# Power.net
KiCad netlist of a schematic drawn in Altium Designer
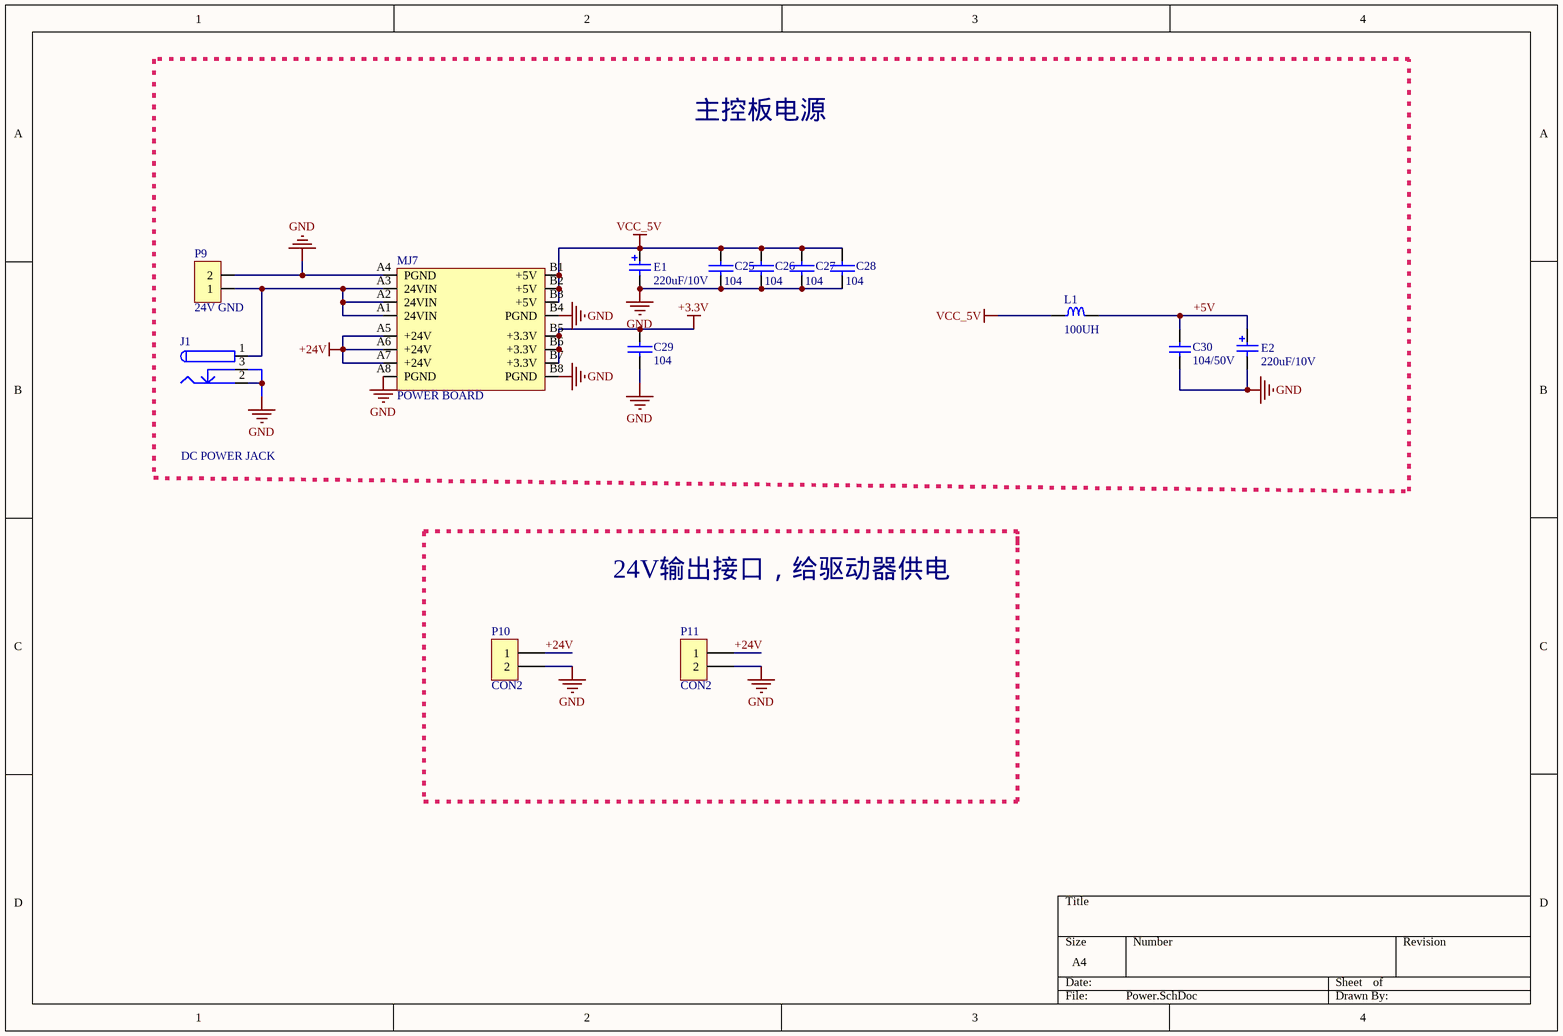
[diagram p0: Power.SchDoc]

(export (version "E")
  (design (tool "Eeschema 10.0.6"))
  (components
    (comp (ref "C25")
      (value "104")
      (footprint "0603C")
      (description "Capacitor")
      (libsource (lib "*") (part "CAP"))
    )
    (comp (ref "C26")
      (value "104")
      (footprint "0603C")
      (description "Capacitor")
      (libsource (lib "*") (part "CAP"))
    )
    (comp (ref "C27")
      (value "104")
      (footprint "0603C")
      (description "Capacitor")
      (libsource (lib "*") (part "CAP"))
    )
    (comp (ref "C28")
      (value "104")
      (footprint "0603C")
      (description "Capacitor")
      (libsource (lib "*") (part "CAP"))
    )
    (comp (ref "C29") (value "104") (footprint "0603C") (libsource (lib "WeiCHGSCH") (part "CAP")))
    (comp (ref "C30")
      (value "104/50V")
      (footprint "0603C")
      (description "瓷片电容,10uF,5%,X7R,50V,0805")
      (libsource (lib "SR SCH Library V02") (part "C10uF/50V-0805"))
    )
    (comp (ref "E1")
      (value "220uF/10V")
      (footprint "3216")
      (description "Bi-Polar Capacitor")
      (libsource (lib "*") (part "电解电容"))
    )
    (comp (ref "E2")
      (value "220uF/10V")
      (footprint "3216")
      (description "Bi-Polar Capacitor")
      (libsource (lib "*") (part "电解电容"))
    )
    (comp (ref "J1")
      (value "DC POWER JACK")
      (footprint "DC-005")
      (libsource (lib "WeiCHGSCH") (part "DC POWER JACK"))
    )
    (comp (ref "L1")
      (value "100UH")
      (footprint "L-SMD7.4*7.4")
      (description "电感")
      (libsource (lib "*") (part "INDUCTOR"))
    )
    (comp (ref "MJ7")
      (value "POWER BOARD")
      (footprint "POWER BOARD")
      (libsource (lib "Block Board Library SCH") (part "J-PW"))
    )
    (comp (ref "P9")
      (value "24V GND")
      (footprint "KF124-2P-3.5")
      (description "欧式接线端子，KF127-5.08-2P,2PIN，5.08mm")
      (libsource (lib "SR SCH Library V02") (part "KF127-5.08-2P"))
    )
    (comp (ref "P10") (value "CON2") (footprint "KF124-2P-3.5") (libsource (lib "WeiCHGSCH") (part "CON2")))
    (comp (ref "P11") (value "CON2") (footprint "KF124-2P-3.5") (libsource (lib "WeiCHGSCH") (part "CON2")))
  )
  (nets
    (net (code "1") (name "+3.3V") (class "Default")
      (node (ref "C29") (pin "2") (pinfunction "2_2") (pintype "passive"))
      (node (ref "MJ7") (pin "B5") (pinfunction "+3.3V_B5") (pintype "passive"))
      (node (ref "MJ7") (pin "B6") (pinfunction "+3.3V_B6") (pintype "passive"))
      (node (ref "MJ7") (pin "B7") (pinfunction "+3.3V_B7") (pintype "passive"))
    )
    (net (code "2") (name "+24V") (class "Default")
      (node (ref "MJ7") (pin "A5") (pinfunction "+24V_A5") (pintype "passive"))
      (node (ref "MJ7") (pin "A6") (pinfunction "+24V_A6") (pintype "passive"))
      (node (ref "MJ7") (pin "A7") (pinfunction "+24V_A7") (pintype "passive"))
      (node (ref "P10") (pin "1") (pinfunction "1_1") (pintype "passive"))
      (node (ref "P11") (pin "1") (pinfunction "1_1") (pintype "passive"))
    )
    (net (code "3") (name "/+5V") (class "Default")
      (node (ref "C30") (pin "2") (pinfunction "2_2") (pintype "passive"))
      (node (ref "E2") (pin "1") (pinfunction "1_1") (pintype "passive"))
      (node (ref "L1") (pin "2") (pinfunction "2_2") (pintype "passive"))
    )
    (net (code "4") (name "GND") (class "Default")
      (node (ref "C25") (pin "2") (pinfunction "2_2") (pintype "passive"))
      (node (ref "C26") (pin "2") (pinfunction "2_2") (pintype "passive"))
      (node (ref "C27") (pin "2") (pinfunction "2_2") (pintype "passive"))
      (node (ref "C28") (pin "2") (pinfunction "2_2") (pintype "passive"))
      (node (ref "C29") (pin "1") (pinfunction "1_1") (pintype "passive"))
      (node (ref "C30") (pin "1") (pinfunction "1_1") (pintype "passive"))
      (node (ref "E1") (pin "2") (pinfunction "2_2") (pintype "passive"))
      (node (ref "E2") (pin "2") (pinfunction "2_2") (pintype "passive"))
      (node (ref "J1") (pin "2") (pinfunction "2_2") (pintype "power_in"))
      (node (ref "J1") (pin "3") (pinfunction "3_3") (pintype "power_in"))
      (node (ref "MJ7") (pin "A4") (pinfunction "PGND_A4") (pintype "passive"))
      (node (ref "MJ7") (pin "A8") (pinfunction "PGND_A8") (pintype "passive"))
      (node (ref "MJ7") (pin "B4") (pinfunction "PGND_B4") (pintype "passive"))
      (node (ref "MJ7") (pin "B8") (pinfunction "PGND_B8") (pintype "passive"))
      (node (ref "P10") (pin "2") (pinfunction "2_2") (pintype "passive"))
      (node (ref "P11") (pin "2") (pinfunction "2_2") (pintype "passive"))
      (node (ref "P9") (pin "2") (pinfunction "2_2") (pintype "passive"))
    )
    (net (code "5") (name "Net-(J1-Pad1)") (class "Default")
      (node (ref "J1") (pin "1") (pinfunction "1_1") (pintype "power_in"))
      (node (ref "MJ7") (pin "A1") (pinfunction "24VIN_A1") (pintype "passive"))
      (node (ref "MJ7") (pin "A2") (pinfunction "24VIN_A2") (pintype "passive"))
      (node (ref "MJ7") (pin "A3") (pinfunction "24VIN_A3") (pintype "passive"))
      (node (ref "P9") (pin "1") (pinfunction "1_1") (pintype "passive"))
    )
    (net (code "6") (name "VCC_5V") (class "Default")
      (node (ref "C25") (pin "1") (pinfunction "1_1") (pintype "passive"))
      (node (ref "C26") (pin "1") (pinfunction "1_1") (pintype "passive"))
      (node (ref "C27") (pin "1") (pinfunction "1_1") (pintype "passive"))
      (node (ref "C28") (pin "1") (pinfunction "1_1") (pintype "passive"))
      (node (ref "E1") (pin "1") (pinfunction "1_1") (pintype "passive"))
      (node (ref "L1") (pin "1") (pinfunction "1_1") (pintype "passive"))
      (node (ref "MJ7") (pin "B1") (pinfunction "+5V_B1") (pintype "passive"))
      (node (ref "MJ7") (pin "B2") (pinfunction "+5V_B2") (pintype "passive"))
      (node (ref "MJ7") (pin "B3") (pinfunction "+5V_B3") (pintype "passive"))
    )
  )
)
